# DECADE-PwmduinoV1.net
KiCad netlist of a schematic drawn in EAGLE
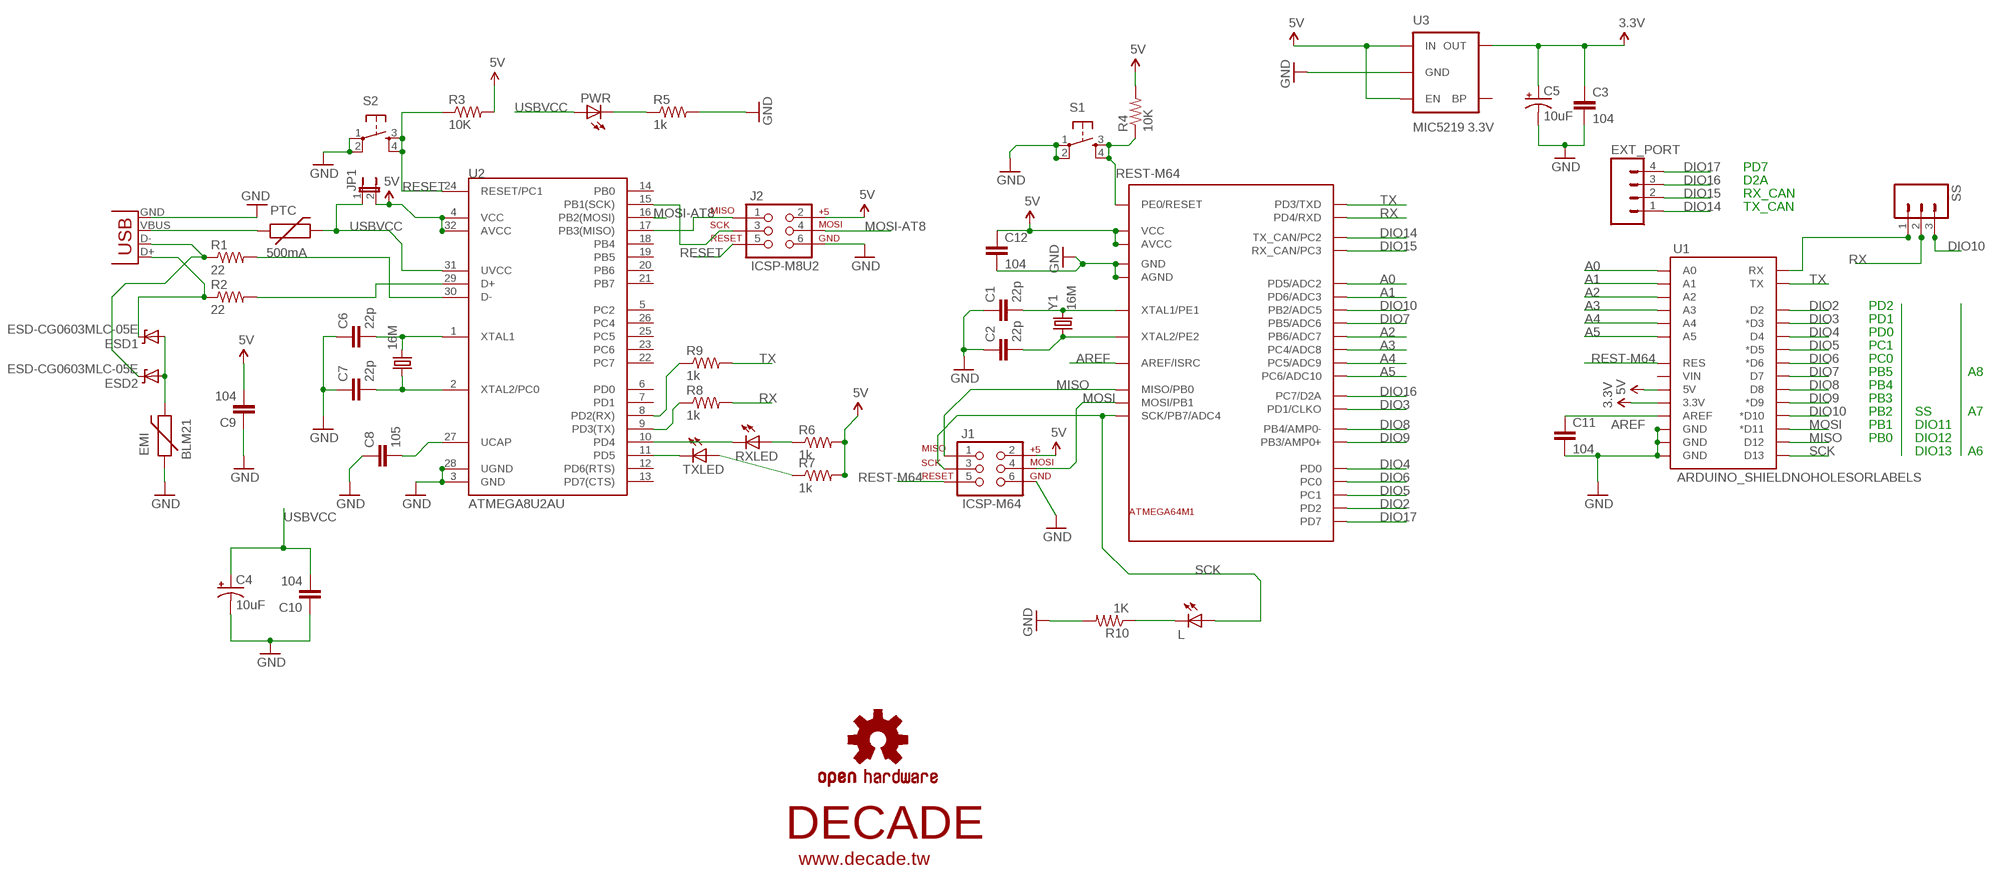
[diagram p0: schematic, sheet 1]

(export (version "E")
  (design (tool "Eeschema 10.0.6"))
  (components
    (comp (ref "16M")
      (value "CRYSTAL5X3")
      (footprint "eagle-import:CRYSTAL-SMD-5X3")
      (libsource (lib "eagle-import") (part "CRYSTAL5X3"))
    )
    (comp (ref "C1")
      (value "22p")
      (footprint "eagle-import:0603-CAP")
      (libsource (lib "eagle-import") (part "CAP0603-CAP"))
    )
    (comp (ref "C2")
      (value "22p")
      (footprint "eagle-import:0603-CAP")
      (libsource (lib "eagle-import") (part "CAP0603-CAP"))
    )
    (comp (ref "C3")
      (value "104")
      (footprint "eagle-import:0603-CAP")
      (libsource (lib "eagle-import") (part "CAP0603-CAP"))
    )
    (comp (ref "C4")
      (value "10uF")
      (footprint "eagle-import:EIA3216-KIT")
      (libsource (lib "eagle-import") (part "CAP_POL1206-KIT"))
    )
    (comp (ref "C5")
      (value "10uF")
      (footprint "eagle-import:EIA3216-KIT")
      (libsource (lib "eagle-import") (part "CAP_POL1206-KIT"))
    )
    (comp (ref "C6")
      (value "22p")
      (footprint "eagle-import:0603-CAP")
      (libsource (lib "eagle-import") (part "CAP0603-CAP"))
    )
    (comp (ref "C7")
      (value "22p")
      (footprint "eagle-import:0603-CAP")
      (libsource (lib "eagle-import") (part "CAP0603-CAP"))
    )
    (comp (ref "C8")
      (value "105")
      (footprint "eagle-import:0603-CAP")
      (libsource (lib "eagle-import") (part "CAP0603-CAP"))
    )
    (comp (ref "C9")
      (value "104")
      (footprint "eagle-import:0603-CAP")
      (libsource (lib "eagle-import") (part "CAP0603-CAP"))
    )
    (comp (ref "C10")
      (value "104")
      (footprint "eagle-import:0603-CAP")
      (libsource (lib "eagle-import") (part "CAP0603-CAP"))
    )
    (comp (ref "C11")
      (value "104")
      (footprint "eagle-import:0603-CAP")
      (libsource (lib "eagle-import") (part "CAP0603-CAP"))
    )
    (comp (ref "C12")
      (value "104")
      (footprint "eagle-import:0603-CAP")
      (libsource (lib "eagle-import") (part "CAP0603-CAP"))
    )
    (comp (ref "EMI")
      (value "BLM21")
      (footprint "eagle-import:PTC-1206")
      (libsource (lib "eagle-import") (part "PTCSMD"))
    )
    (comp (ref "ESD1")
      (value "ESD-CG0603MLC-05E")
      (footprint "eagle-import:SOD-323")
      (libsource (lib "eagle-import") (part "DIODE-ZENER-BZT52"))
    )
    (comp (ref "ESD2")
      (value "ESD-CG0603MLC-05E")
      (footprint "eagle-import:SOD-323")
      (libsource (lib "eagle-import") (part "DIODE-ZENER-BZT52"))
    )
    (comp (ref "EXT_PORT")
      (value "M04LOCK")
      (footprint "eagle-import:1X04_LOCK")
      (libsource (lib "eagle-import") (part "M04LOCK"))
    )
    (comp (ref "J1")
      (value "ICSP-M64")
      (footprint "eagle-import:2X3_LOCK")
      (libsource (lib "eagle-import") (part "AVR_SPI_PRG_62X3_LOCK"))
    )
    (comp (ref "J2")
      (value "ICSP-M8U2")
      (footprint "eagle-import:2X3_LOCK")
      (libsource (lib "eagle-import") (part "AVR_SPI_PRG_62X3_LOCK"))
    )
    (comp (ref "JP1")
      (value "JUMPER-2SMD-NO")
      (footprint "eagle-import:SJ_2S-NO")
      (libsource (lib "eagle-import") (part "JUMPER-2SMD-NO"))
    )
    (comp (ref "L")
      (value "LEDCHIP-LED0603")
      (footprint "eagle-import:CHIP-LED0603")
      (libsource (lib "eagle-import") (part "LEDCHIP-LED0603"))
    )
    (comp (ref "LOGO1")
      (value "OSHW-LOGOL")
      (footprint "eagle-import:OSHW-LOGO-L")
      (libsource (lib "eagle-import") (part "OSHW-LOGOL"))
    )
    (comp (ref "PTC")
      (value "500mA")
      (footprint "eagle-import:SPARKFUN_PTC-1206")
      (libsource (lib "eagle-import") (part "SPARKFUN_PTCSMD"))
    )
    (comp (ref "PWR")
      (value "LEDCHIP-LED0603")
      (footprint "eagle-import:CHIP-LED0603")
      (libsource (lib "eagle-import") (part "LEDCHIP-LED0603"))
    )
    (comp (ref "R1")
      (value "22")
      (footprint "eagle-import:SPARKFUN_0603-RES")
      (libsource (lib "eagle-import") (part "SPARKFUN_RESISTOR0603-RES"))
    )
    (comp (ref "R2")
      (value "22")
      (footprint "eagle-import:SPARKFUN_0603-RES")
      (libsource (lib "eagle-import") (part "SPARKFUN_RESISTOR0603-RES"))
    )
    (comp (ref "R3")
      (value "10K")
      (footprint "eagle-import:SPARKFUN_0603-RES")
      (libsource (lib "eagle-import") (part "SPARKFUN_RESISTOR0603-RES"))
    )
    (comp (ref "R4")
      (value "10K")
      (footprint "eagle-import:SPARKFUN_0603-RES")
      (libsource (lib "eagle-import") (part "SPARKFUN_RESISTOR0603-RES"))
    )
    (comp (ref "R5")
      (value "1k")
      (footprint "eagle-import:SPARKFUN_0603-RES")
      (libsource (lib "eagle-import") (part "SPARKFUN_RESISTOR0603-RES"))
    )
    (comp (ref "R6")
      (value "1k")
      (footprint "eagle-import:SPARKFUN_0603-RES")
      (libsource (lib "eagle-import") (part "SPARKFUN_RESISTOR0603-RES"))
    )
    (comp (ref "R7")
      (value "1k")
      (footprint "eagle-import:SPARKFUN_0603-RES")
      (libsource (lib "eagle-import") (part "SPARKFUN_RESISTOR0603-RES"))
    )
    (comp (ref "R8")
      (value "1k")
      (footprint "eagle-import:SPARKFUN_0603-RES")
      (libsource (lib "eagle-import") (part "SPARKFUN_RESISTOR0603-RES"))
    )
    (comp (ref "R9")
      (value "1k")
      (footprint "eagle-import:SPARKFUN_0603-RES")
      (libsource (lib "eagle-import") (part "SPARKFUN_RESISTOR0603-RES"))
    )
    (comp (ref "R10")
      (value "1K")
      (footprint "eagle-import:SPARKFUN_0603-RES")
      (libsource (lib "eagle-import") (part "SPARKFUN_RESISTOR0603-RES"))
    )
    (comp (ref "RXLED")
      (value "LEDCHIP-LED0603")
      (footprint "eagle-import:CHIP-LED0603")
      (libsource (lib "eagle-import") (part "LEDCHIP-LED0603"))
    )
    (comp (ref "S1")
      (value "TAC_SWITCHPTH")
      (footprint "eagle-import:TACTILE-PTH")
      (libsource (lib "eagle-import") (part "TAC_SWITCHPTH"))
    )
    (comp (ref "S2")
      (value "TAC_SWITCHSMD")
      (footprint "eagle-import:TACTILE_SWITCH_SMD")
      (libsource (lib "eagle-import") (part "TAC_SWITCHSMD"))
    )
    (comp (ref "SS")
      (value "M03LOCK")
      (footprint "eagle-import:1X03_LOCK")
      (libsource (lib "eagle-import") (part "M03LOCK"))
    )
    (comp (ref "TXLED")
      (value "LEDCHIP-LED0603")
      (footprint "eagle-import:CHIP-LED0603")
      (libsource (lib "eagle-import") (part "LEDCHIP-LED0603"))
    )
    (comp (ref "U$1")
      (value "DECADE-ATMEGA64M1")
      (footprint "eagle-import:DECADE-QFN-32")
      (libsource (lib "eagle-import") (part "DECADE-ATMEGA64M1"))
    )
    (comp (ref "U$2")
      (value "DECADE-LOGO-SMALL")
      (footprint "eagle-import:DECADE-LOGO-SMALL")
      (libsource (lib "eagle-import") (part "DECADE-LOGO-SMALL"))
    )
    (comp (ref "U1")
      (value "ARDUINO_SHIELDNOHOLESORLABELS")
      (footprint "eagle-import:DUEMILANOVE_SHIELD_NOHOLES_NOLABELS")
      (libsource (lib "eagle-import") (part "ARDUINO_SHIELDNOHOLESORLABELS"))
    )
    (comp (ref "U2")
      (value "ATMEGA8U2AU")
      (footprint "eagle-import:TQFP32-08")
      (libsource (lib "eagle-import") (part "ATMEGA8U2AU"))
    )
    (comp (ref "U3")
      (value "MIC5219 3.3V")
      (footprint "eagle-import:SOT23-5")
      (libsource (lib "eagle-import") (part "V_REG_MIC52193.3V"))
    )
    (comp (ref "X1")
      (value "SPARKFUN_USBOLD")
      (footprint "eagle-import:SPARKFUN_USB-MINIB-OLD")
      (libsource (lib "eagle-import") (part "SPARKFUN_USBOLD"))
    )
    (comp (ref "Y1")
      (value "16M")
      (footprint "eagle-import:CRYSTAL-SMD-5X3")
      (libsource (lib "eagle-import") (part "CRYSTAL5X3"))
    )
  )
  (nets
    (net (code "1") (name "/A0") (class "Default")
      (node (ref "U$1") (pin "13") (pinfunction "PD5/ADC2_13") (pintype "bidirectional"))
      (node (ref "U1") (pin "A0") (pinfunction "A0_A0") (pintype "bidirectional"))
    )
    (net (code "2") (name "/A1") (class "Default")
      (node (ref "U$1") (pin "14") (pinfunction "PD6/ADC3_14") (pintype "bidirectional"))
      (node (ref "U1") (pin "A1") (pinfunction "A1_A1") (pintype "bidirectional"))
    )
    (net (code "3") (name "/A2") (class "Default")
      (node (ref "U$1") (pin "27") (pinfunction "PB6/ADC7_27") (pintype "bidirectional"))
      (node (ref "U1") (pin "A2") (pinfunction "A2_A2") (pintype "bidirectional"))
    )
    (net (code "4") (name "/A3") (class "Default")
      (node (ref "U$1") (pin "17") (pinfunction "PC4/ADC8_17") (pintype "bidirectional"))
      (node (ref "U1") (pin "A3") (pinfunction "A3_A3") (pintype "bidirectional"))
    )
    (net (code "5") (name "/A4") (class "Default")
      (node (ref "U$1") (pin "18") (pinfunction "PC5/ADC9_18") (pintype "bidirectional"))
      (node (ref "U1") (pin "A4") (pinfunction "A4_A4") (pintype "bidirectional"))
    )
    (net (code "6") (name "/A5") (class "Default")
      (node (ref "U$1") (pin "22") (pinfunction "PC6/ADC10_22") (pintype "bidirectional"))
      (node (ref "U1") (pin "A5") (pinfunction "A5_A5") (pintype "bidirectional"))
    )
    (net (code "7") (name "/AREF") (class "Default")
      (node (ref "C11") (pin "1") (pinfunction "1_1") (pintype "passive"))
      (node (ref "U$1") (pin "21") (pinfunction "AREF/ISRC_21") (pintype "bidirectional"))
      (node (ref "U1") (pin "AREF") (pinfunction "AREF_AREF") (pintype "bidirectional"))
    )
    (net (code "8") (name "/DIO2") (class "Default")
      (node (ref "U$1") (pin "1") (pinfunction "PD2_1") (pintype "bidirectional"))
      (node (ref "U1") (pin "D2") (pinfunction "D2_D2") (pintype "bidirectional"))
    )
    (net (code "9") (name "/DIO3") (class "Default")
      (node (ref "U$1") (pin "32") (pinfunction "PD1/CLKO_32") (pintype "bidirectional"))
      (node (ref "U1") (pin "D3") (pinfunction "*D3_D3") (pintype "bidirectional"))
    )
    (net (code "10") (name "/DIO4") (class "Default")
      (node (ref "U$1") (pin "29") (pinfunction "PD0_29") (pintype "bidirectional"))
      (node (ref "U1") (pin "D4") (pinfunction "D4_D4") (pintype "bidirectional"))
    )
    (net (code "11") (name "/DIO5") (class "Default")
      (node (ref "U$1") (pin "3") (pinfunction "PC1_3") (pintype "bidirectional"))
      (node (ref "U1") (pin "D5") (pinfunction "*D5_D5") (pintype "bidirectional"))
    )
    (net (code "12") (name "/DIO6") (class "Default")
      (node (ref "U$1") (pin "30") (pinfunction "PC0_30") (pintype "bidirectional"))
      (node (ref "U1") (pin "D6") (pinfunction "*D6_D6") (pintype "bidirectional"))
    )
    (net (code "13") (name "/DIO7") (class "Default")
      (node (ref "U$1") (pin "26") (pinfunction "PB5/ADC6_26") (pintype "bidirectional"))
      (node (ref "U1") (pin "D7") (pinfunction "D7_D7") (pintype "bidirectional"))
    )
    (net (code "14") (name "/DIO8") (class "Default")
      (node (ref "U$1") (pin "24") (pinfunction "PB4/AMP0-_24") (pintype "bidirectional"))
      (node (ref "U1") (pin "D8") (pinfunction "D8_D8") (pintype "bidirectional"))
    )
    (net (code "15") (name "/DIO9") (class "Default")
      (node (ref "U$1") (pin "23") (pinfunction "PB3/AMP0+_23") (pintype "bidirectional"))
      (node (ref "U1") (pin "D9") (pinfunction "*D9_D9") (pintype "bidirectional"))
    )
    (net (code "16") (name "/DIO10") (class "Default")
      (node (ref "SS") (pin "3") (pinfunction "3_3") (pintype "passive"))
      (node (ref "U$1") (pin "16") (pinfunction "PB2/ADC5_16") (pintype "bidirectional"))
      (node (ref "U1") (pin "D10") (pinfunction "*D10_D10") (pintype "bidirectional"))
    )
    (net (code "17") (name "/DIO14") (class "Default")
      (node (ref "EXT_PORT") (pin "1") (pinfunction "1_1") (pintype "passive"))
      (node (ref "U$1") (pin "6") (pinfunction "TX_CAN/PC2_6") (pintype "bidirectional"))
    )
    (net (code "18") (name "/DIO15") (class "Default")
      (node (ref "EXT_PORT") (pin "2") (pinfunction "2_2") (pintype "passive"))
      (node (ref "U$1") (pin "7") (pinfunction "RX_CAN/PC3_7") (pintype "bidirectional"))
    )
    (net (code "19") (name "/DIO16") (class "Default")
      (node (ref "EXT_PORT") (pin "3") (pinfunction "3_3") (pintype "passive"))
      (node (ref "U$1") (pin "25") (pinfunction "PC7/D2A_25") (pintype "bidirectional"))
    )
    (net (code "20") (name "/DIO17") (class "Default")
      (node (ref "EXT_PORT") (pin "4") (pinfunction "4_4") (pintype "passive"))
      (node (ref "U$1") (pin "15") (pinfunction "PD7_15") (pintype "bidirectional"))
    )
    (net (code "21") (name "/MISO") (class "Default")
      (node (ref "J1") (pin "1") (pinfunction "1_1") (pintype "passive"))
      (node (ref "U$1") (pin "8") (pinfunction "MISO/PB0_8") (pintype "bidirectional"))
      (node (ref "U1") (pin "D12") (pinfunction "D12_D12") (pintype "bidirectional"))
    )
    (net (code "22") (name "/MOSI") (class "Default")
      (node (ref "J1") (pin "4") (pinfunction "4_4") (pintype "passive"))
      (node (ref "U$1") (pin "9") (pinfunction "MOSI/PB1_9") (pintype "bidirectional"))
      (node (ref "U1") (pin "D11") (pinfunction "*D11_D11") (pintype "bidirectional"))
    )
    (net (code "23") (name "/MOSI-AT8") (class "Default")
      (node (ref "J2") (pin "4") (pinfunction "4_4") (pintype "passive"))
      (node (ref "U2") (pin "16") (pinfunction "PB2(MOSI)_16") (pintype "bidirectional"))
    )
    (net (code "24") (name "/RESET") (class "Default")
      (node (ref "J2") (pin "5") (pinfunction "5_5") (pintype "passive"))
      (node (ref "R3") (pin "1") (pinfunction "1_1") (pintype "passive"))
      (node (ref "S2") (pin "3") (pinfunction "3_3") (pintype "passive"))
      (node (ref "S2") (pin "4") (pinfunction "4_4") (pintype "passive"))
      (node (ref "U2") (pin "24") (pinfunction "RESET/PC1_24") (pintype "bidirectional"))
    )
    (net (code "25") (name "/REST-M64") (class "Default")
      (node (ref "J1") (pin "5") (pinfunction "5_5") (pintype "passive"))
      (node (ref "R4") (pin "1") (pinfunction "1_1") (pintype "passive"))
      (node (ref "S1") (pin "3") (pinfunction "3_3") (pintype "passive"))
      (node (ref "S1") (pin "4") (pinfunction "4_4") (pintype "passive"))
      (node (ref "U$1") (pin "31") (pinfunction "PE0/RESET_31") (pintype "bidirectional"))
      (node (ref "U1") (pin "RES") (pinfunction "RES_RES") (pintype "bidirectional"))
    )
    (net (code "26") (name "/RX") (class "Default")
      (node (ref "R8") (pin "2") (pinfunction "2_2") (pintype "passive"))
      (node (ref "SS") (pin "2") (pinfunction "2_2") (pintype "passive"))
      (node (ref "U$1") (pin "12") (pinfunction "PD4/RXD_12") (pintype "bidirectional"))
    )
    (net (code "27") (name "/SCK") (class "Default")
      (node (ref "J1") (pin "3") (pinfunction "3_3") (pintype "passive"))
      (node (ref "L") (pin "A") (pinfunction "A_A") (pintype "passive"))
      (node (ref "U$1") (pin "28") (pinfunction "SCK/PB7/ADC4_28") (pintype "bidirectional"))
      (node (ref "U1") (pin "D13") (pinfunction "D13_D13") (pintype "bidirectional"))
    )
    (net (code "28") (name "/TX") (class "Default")
      (node (ref "R9") (pin "2") (pinfunction "2_2") (pintype "passive"))
      (node (ref "U$1") (pin "2") (pinfunction "PD3/TXD_2") (pintype "bidirectional"))
      (node (ref "U1") (pin "TX") (pinfunction "TX_TX") (pintype "bidirectional"))
    )
    (net (code "29") (name "/USBVCC") (class "Default")
      (node (ref "C10") (pin "2") (pinfunction "2_2") (pintype "passive"))
      (node (ref "C4") (pin "A") (pinfunction "+_A") (pintype "passive"))
      (node (ref "JP1") (pin "1") (pinfunction "1_1") (pintype "passive"))
      (node (ref "PTC") (pin "2") (pinfunction "2_2") (pintype "bidirectional"))
      (node (ref "PWR") (pin "A") (pinfunction "A_A") (pintype "passive"))
      (node (ref "U2") (pin "31") (pinfunction "UVCC_31") (pintype "bidirectional"))
    )
    (net (code "30") (name "3.3V") (class "Default")
      (node (ref "C3") (pin "1") (pinfunction "1_1") (pintype "passive"))
      (node (ref "C5") (pin "A") (pinfunction "+_A") (pintype "passive"))
      (node (ref "U1") (pin "3.3V") (pinfunction "3.3V_3.3V") (pintype "bidirectional"))
      (node (ref "U3") (pin "5") (pinfunction "OUT_5") (pintype "passive"))
    )
    (net (code "31") (name "5V") (class "Default")
      (node (ref "C12") (pin "1") (pinfunction "1_1") (pintype "passive"))
      (node (ref "C9") (pin "2") (pinfunction "2_2") (pintype "passive"))
      (node (ref "J1") (pin "2") (pinfunction "2_2") (pintype "passive"))
      (node (ref "J2") (pin "2") (pinfunction "2_2") (pintype "passive"))
      (node (ref "JP1") (pin "2") (pinfunction "2_2") (pintype "passive"))
      (node (ref "R3") (pin "2") (pinfunction "2_2") (pintype "passive"))
      (node (ref "R4") (pin "2") (pinfunction "2_2") (pintype "passive"))
      (node (ref "R6") (pin "2") (pinfunction "2_2") (pintype "passive"))
      (node (ref "R7") (pin "2") (pinfunction "2_2") (pintype "passive"))
      (node (ref "U$1") (pin "19") (pinfunction "AVCC_19") (pintype "bidirectional"))
      (node (ref "U$1") (pin "4") (pinfunction "VCC_4") (pintype "bidirectional"))
      (node (ref "U1") (pin "5V") (pinfunction "5V_5V") (pintype "bidirectional"))
      (node (ref "U2") (pin "32") (pinfunction "AVCC_32") (pintype "bidirectional"))
      (node (ref "U2") (pin "4") (pinfunction "VCC_4") (pintype "bidirectional"))
      (node (ref "U3") (pin "1") (pinfunction "IN_1") (pintype "input"))
      (node (ref "U3") (pin "3") (pinfunction "EN_3") (pintype "input"))
    )
    (net (code "32") (name "GND") (class "Default")
      (node (ref "C1") (pin "1") (pinfunction "1_1") (pintype "passive"))
      (node (ref "C10") (pin "1") (pinfunction "1_1") (pintype "passive"))
      (node (ref "C11") (pin "2") (pinfunction "2_2") (pintype "passive"))
      (node (ref "C12") (pin "2") (pinfunction "2_2") (pintype "passive"))
      (node (ref "C2") (pin "1") (pinfunction "1_1") (pintype "passive"))
      (node (ref "C3") (pin "2") (pinfunction "2_2") (pintype "passive"))
      (node (ref "C4") (pin "C") (pinfunction "-_C") (pintype "passive"))
      (node (ref "C5") (pin "C") (pinfunction "-_C") (pintype "passive"))
      (node (ref "C6") (pin "1") (pinfunction "1_1") (pintype "passive"))
      (node (ref "C7") (pin "1") (pinfunction "1_1") (pintype "passive"))
      (node (ref "C8") (pin "1") (pinfunction "1_1") (pintype "passive"))
      (node (ref "C9") (pin "1") (pinfunction "1_1") (pintype "passive"))
      (node (ref "EMI") (pin "1") (pinfunction "1_1") (pintype "bidirectional"))
      (node (ref "J1") (pin "6") (pinfunction "6_6") (pintype "passive"))
      (node (ref "J2") (pin "6") (pinfunction "6_6") (pintype "passive"))
      (node (ref "R10") (pin "2") (pinfunction "2_2") (pintype "passive"))
      (node (ref "R5") (pin "2") (pinfunction "2_2") (pintype "passive"))
      (node (ref "S1") (pin "1") (pinfunction "1_1") (pintype "passive"))
      (node (ref "S1") (pin "2") (pinfunction "2_2") (pintype "passive"))
      (node (ref "S2") (pin "1") (pinfunction "1_1") (pintype "passive"))
      (node (ref "S2") (pin "2") (pinfunction "2_2") (pintype "passive"))
      (node (ref "U$1") (pin "20") (pinfunction "AGND_20") (pintype "bidirectional"))
      (node (ref "U$1") (pin "5") (pinfunction "GND_5") (pintype "bidirectional"))
      (node (ref "U1") (pin "GND@0") (pinfunction "GND_GND@0") (pintype "bidirectional"))
      (node (ref "U1") (pin "GND@1") (pinfunction "GND_GND@1") (pintype "bidirectional"))
      (node (ref "U1") (pin "GND@2") (pinfunction "GND_GND@2") (pintype "bidirectional"))
      (node (ref "U2") (pin "28") (pinfunction "UGND_28") (pintype "bidirectional"))
      (node (ref "U2") (pin "3") (pinfunction "GND_3") (pintype "bidirectional"))
      (node (ref "U3") (pin "2") (pinfunction "GND_2") (pintype "input"))
      (node (ref "X1") (pin "GND") (pinfunction "GND_GND") (pintype "bidirectional"))
    )
    (net (code "33") (name "Net-(16M-2)") (class "Default")
      (node (ref "16M") (pin "3") (pinfunction "2_3") (pintype "passive"))
      (node (ref "C6") (pin "2") (pinfunction "2_2") (pintype "passive"))
      (node (ref "U2") (pin "1") (pinfunction "XTAL1_1") (pintype "bidirectional"))
    )
    (net (code "34") (name "Net-(ESD1-A)") (class "Default")
      (node (ref "EMI") (pin "2") (pinfunction "2_2") (pintype "bidirectional"))
      (node (ref "ESD1") (pin "2") (pinfunction "A_2") (pintype "passive"))
      (node (ref "ESD2") (pin "2") (pinfunction "A_2") (pintype "passive"))
    )
    (net (code "35") (name "Net-(ESD1-C)") (class "Default")
      (node (ref "ESD1") (pin "1") (pinfunction "C_1") (pintype "passive"))
      (node (ref "R2") (pin "1") (pinfunction "1_1") (pintype "passive"))
      (node (ref "X1") (pin "D+") (pinfunction "D+_D+") (pintype "bidirectional"))
    )
    (net (code "36") (name "Net-(ESD2-C)") (class "Default")
      (node (ref "ESD2") (pin "1") (pinfunction "C_1") (pintype "passive"))
      (node (ref "R1") (pin "1") (pinfunction "1_1") (pintype "passive"))
      (node (ref "X1") (pin "D-") (pinfunction "D-_D-") (pintype "bidirectional"))
    )
    (net (code "37") (name "Net-(L-PadC)") (class "Default")
      (node (ref "L") (pin "C") (pinfunction "C_C") (pintype "passive"))
      (node (ref "R10") (pin "1") (pinfunction "1_1") (pintype "passive"))
    )
    (net (code "38") (name "Net-(PTC-Pad1)") (class "Default")
      (node (ref "PTC") (pin "1") (pinfunction "1_1") (pintype "bidirectional"))
      (node (ref "X1") (pin "VBUS") (pinfunction "VBUS_VBUS") (pintype "bidirectional"))
    )
    (net (code "39") (name "Net-(PWR-PadC)") (class "Default")
      (node (ref "PWR") (pin "C") (pinfunction "C_C") (pintype "passive"))
      (node (ref "R5") (pin "1") (pinfunction "1_1") (pintype "passive"))
    )
    (net (code "40") (name "Net-(R6-Pad1)") (class "Default")
      (node (ref "R6") (pin "1") (pinfunction "1_1") (pintype "passive"))
      (node (ref "RXLED") (pin "A") (pinfunction "A_A") (pintype "passive"))
    )
    (net (code "41") (name "Net-(R7-Pad1)") (class "Default")
      (node (ref "R7") (pin "1") (pinfunction "1_1") (pintype "passive"))
      (node (ref "TXLED") (pin "A") (pinfunction "A_A") (pintype "passive"))
    )
    (net (code "42") (name "Net-(SS-Pad1)") (class "Default")
      (node (ref "SS") (pin "1") (pinfunction "1_1") (pintype "passive"))
      (node (ref "U1") (pin "RX") (pinfunction "RX_RX") (pintype "bidirectional"))
    )
    (net (code "43") (name "Net-(U$1-XTAL1{slash}PE1)") (class "Default")
      (node (ref "C1") (pin "2") (pinfunction "2_2") (pintype "passive"))
      (node (ref "U$1") (pin "10") (pinfunction "XTAL1/PE1_10") (pintype "bidirectional"))
      (node (ref "Y1") (pin "3") (pinfunction "2_3") (pintype "passive"))
    )
    (net (code "44") (name "Net-(U$1-XTAL2{slash}PE2)") (class "Default")
      (node (ref "C2") (pin "2") (pinfunction "2_2") (pintype "passive"))
      (node (ref "U$1") (pin "11") (pinfunction "XTAL2/PE2_11") (pintype "bidirectional"))
      (node (ref "Y1") (pin "1") (pinfunction "1_1") (pintype "passive"))
    )
    (net (code "45") (name "Net-(U2-D+)") (class "Default")
      (node (ref "R2") (pin "2") (pinfunction "2_2") (pintype "passive"))
      (node (ref "U2") (pin "29") (pinfunction "D+_29") (pintype "bidirectional"))
    )
    (net (code "46") (name "Net-(U2-D-)") (class "Default")
      (node (ref "R1") (pin "2") (pinfunction "2_2") (pintype "passive"))
      (node (ref "U2") (pin "30") (pinfunction "D-_30") (pintype "bidirectional"))
    )
    (net (code "47") (name "Net-(U2-PB1(SCK))") (class "Default")
      (node (ref "J2") (pin "3") (pinfunction "3_3") (pintype "passive"))
      (node (ref "U2") (pin "15") (pinfunction "PB1(SCK)_15") (pintype "bidirectional"))
    )
    (net (code "48") (name "Net-(U2-PB3(MISO))") (class "Default")
      (node (ref "J2") (pin "1") (pinfunction "1_1") (pintype "passive"))
      (node (ref "U2") (pin "17") (pinfunction "PB3(MISO)_17") (pintype "bidirectional"))
    )
    (net (code "49") (name "Net-(U2-PD2(RX))") (class "Default")
      (node (ref "R9") (pin "1") (pinfunction "1_1") (pintype "passive"))
      (node (ref "U2") (pin "8") (pinfunction "PD2(RX)_8") (pintype "bidirectional"))
    )
    (net (code "50") (name "Net-(U2-PD3(TX))") (class "Default")
      (node (ref "R8") (pin "1") (pinfunction "1_1") (pintype "passive"))
      (node (ref "U2") (pin "9") (pinfunction "PD3(TX)_9") (pintype "bidirectional"))
    )
    (net (code "51") (name "Net-(U2-PD4)") (class "Default")
      (node (ref "RXLED") (pin "C") (pinfunction "C_C") (pintype "passive"))
      (node (ref "U2") (pin "10") (pinfunction "PD4_10") (pintype "bidirectional"))
    )
    (net (code "52") (name "Net-(U2-PD5)") (class "Default")
      (node (ref "TXLED") (pin "C") (pinfunction "C_C") (pintype "passive"))
      (node (ref "U2") (pin "11") (pinfunction "PD5_11") (pintype "bidirectional"))
    )
    (net (code "53") (name "Net-(U2-UCAP)") (class "Default")
      (node (ref "C8") (pin "2") (pinfunction "2_2") (pintype "passive"))
      (node (ref "U2") (pin "27") (pinfunction "UCAP_27") (pintype "bidirectional"))
    )
    (net (code "54") (name "Net-(U2-XTAL2{slash}PC0)") (class "Default")
      (node (ref "16M") (pin "1") (pinfunction "1_1") (pintype "passive"))
      (node (ref "C7") (pin "2") (pinfunction "2_2") (pintype "passive"))
      (node (ref "U2") (pin "2") (pinfunction "XTAL2/PC0_2") (pintype "bidirectional"))
    )
    (net (code "55") (name "unconnected-(U1-PadVIN)") (class "Default")
      (node (ref "U1") (pin "VIN") (pinfunction "VIN_VIN") (pintype "bidirectional"))
    )
    (net (code "56") (name "unconnected-(U2-PB0-Pad14)") (class "Default")
      (node (ref "U2") (pin "14") (pinfunction "PB0_14") (pintype "bidirectional"))
    )
    (net (code "57") (name "unconnected-(U2-PB4-Pad18)") (class "Default")
      (node (ref "U2") (pin "18") (pinfunction "PB4_18") (pintype "bidirectional"))
    )
    (net (code "58") (name "unconnected-(U2-PB5-Pad19)") (class "Default")
      (node (ref "U2") (pin "19") (pinfunction "PB5_19") (pintype "bidirectional"))
    )
    (net (code "59") (name "unconnected-(U2-PB6-Pad20)") (class "Default")
      (node (ref "U2") (pin "20") (pinfunction "PB6_20") (pintype "bidirectional"))
    )
    (net (code "60") (name "unconnected-(U2-PB7-Pad21)") (class "Default")
      (node (ref "U2") (pin "21") (pinfunction "PB7_21") (pintype "bidirectional"))
    )
    (net (code "61") (name "unconnected-(U2-PC2-Pad5)") (class "Default")
      (node (ref "U2") (pin "5") (pinfunction "PC2_5") (pintype "bidirectional"))
    )
    (net (code "62") (name "unconnected-(U2-PC4-Pad26)") (class "Default")
      (node (ref "U2") (pin "26") (pinfunction "PC4_26") (pintype "bidirectional"))
    )
    (net (code "63") (name "unconnected-(U2-PC5-Pad25)") (class "Default")
      (node (ref "U2") (pin "25") (pinfunction "PC5_25") (pintype "bidirectional"))
    )
    (net (code "64") (name "unconnected-(U2-PC6-Pad23)") (class "Default")
      (node (ref "U2") (pin "23") (pinfunction "PC6_23") (pintype "bidirectional"))
    )
    (net (code "65") (name "unconnected-(U2-PC7-Pad22)") (class "Default")
      (node (ref "U2") (pin "22") (pinfunction "PC7_22") (pintype "bidirectional"))
    )
    (net (code "66") (name "unconnected-(U2-PD0-Pad6)") (class "Default")
      (node (ref "U2") (pin "6") (pinfunction "PD0_6") (pintype "bidirectional"))
    )
    (net (code "67") (name "unconnected-(U2-PD1-Pad7)") (class "Default")
      (node (ref "U2") (pin "7") (pinfunction "PD1_7") (pintype "bidirectional"))
    )
    (net (code "68") (name "unconnected-(U2-PD6(RTS)-Pad12)") (class "Default")
      (node (ref "U2") (pin "12") (pinfunction "PD6(RTS)_12") (pintype "bidirectional"))
    )
    (net (code "69") (name "unconnected-(U2-PD7(CTS)-Pad13)") (class "Default")
      (node (ref "U2") (pin "13") (pinfunction "PD7(CTS)_13") (pintype "bidirectional"))
    )
    (net (code "70") (name "unconnected-(U3-BP-Pad4)") (class "Default")
      (node (ref "U3") (pin "4") (pinfunction "BP_4") (pintype "input"))
    )
  )
)
